# SPEEDuino_v1_0.net
KiCad netlist of a schematic drawn in EAGLE
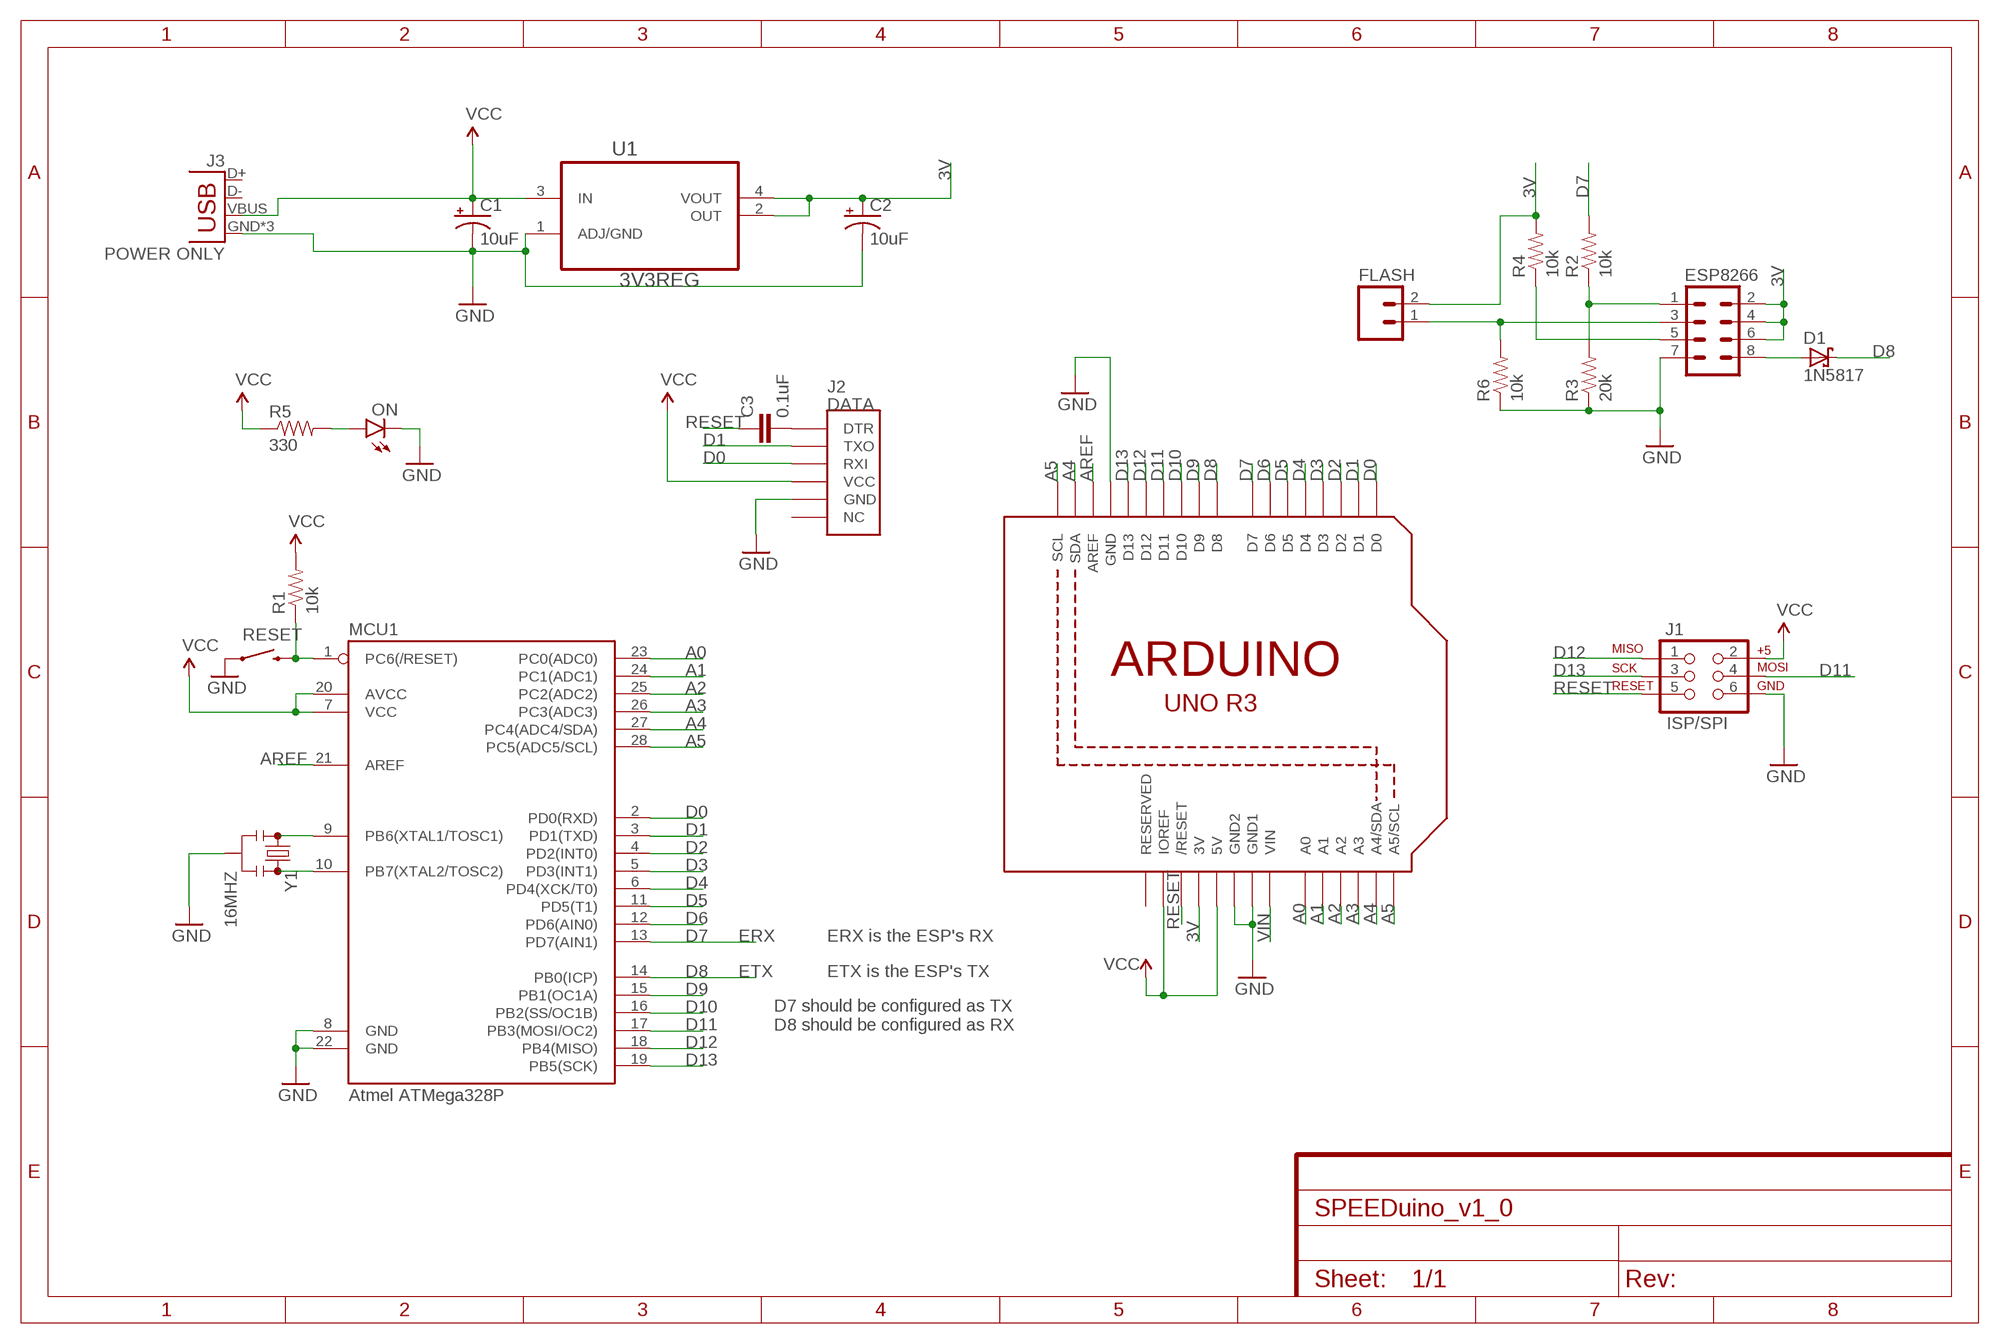
[diagram p0: schematic, sheet 1]

(export (version "E")
  (design (tool "Eeschema 10.0.6"))
  (components
    (comp (ref "C1")
      (value "10uF")
      (footprint "eagle-import:EIA3216-KIT")
      (libsource (lib "eagle-import") (part "CAP_POL1206-KIT"))
    )
    (comp (ref "C2")
      (value "10uF")
      (footprint "eagle-import:EIA3216-KIT")
      (libsource (lib "eagle-import") (part "CAP_POL1206-KIT"))
    )
    (comp (ref "C3")
      (value "0.1uF")
      (footprint "eagle-import:1206")
      (libsource (lib "eagle-import") (part "CAP1206"))
    )
    (comp (ref "D1")
      (value "1N5817")
      (footprint "eagle-import:DO41-10")
      (libsource (lib "eagle-import") (part "1N5817"))
    )
    (comp (ref "ESP8266")
      (value "M04X2")
      (footprint "eagle-import:2X4")
      (libsource (lib "eagle-import") (part "M04X2"))
    )
    (comp (ref "FLASH")
      (value "M02LOCK")
      (footprint "eagle-import:1X02_LOCK")
      (libsource (lib "eagle-import") (part "M02LOCK"))
    )
    (comp (ref "J1")
      (value "ISP/SPI")
      (footprint "eagle-import:2X3")
      (libsource (lib "eagle-import") (part "AVR_SPI_PRG_6PTH"))
    )
    (comp (ref "J2")
      (value "DATA")
      (footprint "eagle-import:CP2102_DEVICE_SIDE")
      (libsource (lib "eagle-import") (part "CP2102_DEVICECP"))
    )
    (comp (ref "J3")
      (value "POWER ONLY")
      (footprint "eagle-import:USB-MICROB")
      (libsource (lib "eagle-import") (part "USB-MICROB"))
    )
    (comp (ref "MCU1")
      (value "Atmel ATMega328P")
      (footprint "eagle-import:DIL28-3")
      (libsource (lib "eagle-import") (part "ATMEGA328P_PDIP"))
    )
    (comp (ref "ON")
      (value "LED3MM")
      (footprint "eagle-import:LED3MM")
      (libsource (lib "eagle-import") (part "LED3MM"))
    )
    (comp (ref "R1")
      (value "10k")
      (footprint "eagle-import:1206")
      (libsource (lib "eagle-import") (part "RESISTOR1206"))
    )
    (comp (ref "R2")
      (value "10k")
      (footprint "eagle-import:1206")
      (libsource (lib "eagle-import") (part "RESISTOR1206"))
    )
    (comp (ref "R3")
      (value "20k")
      (footprint "eagle-import:1206")
      (libsource (lib "eagle-import") (part "RESISTOR1206"))
    )
    (comp (ref "R4")
      (value "10k")
      (footprint "eagle-import:1206")
      (libsource (lib "eagle-import") (part "RESISTOR1206"))
    )
    (comp (ref "R5")
      (value "330")
      (footprint "eagle-import:1206")
      (libsource (lib "eagle-import") (part "RESISTOR1206"))
    )
    (comp (ref "R6")
      (value "10k")
      (footprint "eagle-import:1206")
      (libsource (lib "eagle-import") (part "RESISTOR1206"))
    )
    (comp (ref "RESET")
      (value "SWITCH-MOMENTARY-2PTH")
      (footprint "eagle-import:TACTILE-PTH")
      (libsource (lib "eagle-import") (part "SWITCH-MOMENTARY-2PTH"))
    )
    (comp (ref "U1")
      (value "3V3REG")
      (footprint "eagle-import:SOT230P696X180-4N")
      (fields (field (name "MPN") "LM1117MP-3.3"))
      (libsource (lib "eagle-import") (part "LM1117MP-3.3"))
    )
    (comp (ref "U2")
      (value "ARDUINOR3-DIMENSION")
      (footprint "eagle-import:ARDUINOR3")
      (libsource (lib "eagle-import") (part "ARDUINOR3-DIMENSION"))
    )
    (comp (ref "Y1")
      (value "16MHZ")
      (footprint "eagle-import:RESONATOR-SMD")
      (libsource (lib "eagle-import") (part "RESONATOR16MHZ"))
    )
  )
  (nets
    (net (code "1") (name "/3V") (class "Default")
      (node (ref "C2") (pin "A") (pinfunction "+_A") (pintype "passive"))
      (node (ref "ESP8266") (pin "2") (pinfunction "2_2") (pintype "passive"))
      (node (ref "ESP8266") (pin "4") (pinfunction "4_4") (pintype "passive"))
      (node (ref "ESP8266") (pin "6") (pinfunction "6_6") (pintype "passive"))
      (node (ref "FLASH") (pin "2") (pinfunction "2_2") (pintype "passive"))
      (node (ref "R4") (pin "2") (pinfunction "2_2") (pintype "passive"))
      (node (ref "U1") (pin "2") (pinfunction "OUT_2") (pintype "output"))
      (node (ref "U1") (pin "4") (pinfunction "VOUT_4") (pintype "output"))
      (node (ref "U2") (pin "3V") (pinfunction "3V_3V") (pintype "power_in"))
    )
    (net (code "2") (name "/A0") (class "Default")
      (node (ref "MCU1") (pin "23") (pinfunction "PC0(ADC0)_23") (pintype "bidirectional"))
      (node (ref "U2") (pin "A0") (pinfunction "A0_A0") (pintype "bidirectional"))
    )
    (net (code "3") (name "/A1") (class "Default")
      (node (ref "MCU1") (pin "24") (pinfunction "PC1(ADC1)_24") (pintype "bidirectional"))
      (node (ref "U2") (pin "A1") (pinfunction "A1_A1") (pintype "bidirectional"))
    )
    (net (code "4") (name "/A2") (class "Default")
      (node (ref "MCU1") (pin "25") (pinfunction "PC2(ADC2)_25") (pintype "bidirectional"))
      (node (ref "U2") (pin "A2") (pinfunction "A2_A2") (pintype "bidirectional"))
    )
    (net (code "5") (name "/A3") (class "Default")
      (node (ref "MCU1") (pin "26") (pinfunction "PC3(ADC3)_26") (pintype "bidirectional"))
      (node (ref "U2") (pin "A3") (pinfunction "A3_A3") (pintype "bidirectional"))
    )
    (net (code "6") (name "/A4") (class "Default")
      (node (ref "MCU1") (pin "27") (pinfunction "PC4(ADC4/SDA)_27") (pintype "bidirectional"))
      (node (ref "U2") (pin "A4") (pinfunction "A4/SDA_A4") (pintype "bidirectional"))
      (node (ref "U2") (pin "SDA") (pinfunction "SDA_SDA") (pintype "bidirectional"))
    )
    (net (code "7") (name "/A5") (class "Default")
      (node (ref "MCU1") (pin "28") (pinfunction "PC5(ADC5/SCL)_28") (pintype "bidirectional"))
      (node (ref "U2") (pin "A5") (pinfunction "A5/SCL_A5") (pintype "bidirectional"))
      (node (ref "U2") (pin "SCL") (pinfunction "SCL_SCL") (pintype "bidirectional"))
    )
    (net (code "8") (name "/AREF") (class "Default")
      (node (ref "MCU1") (pin "21") (pinfunction "AREF_21") (pintype "bidirectional"))
      (node (ref "U2") (pin "AREF") (pinfunction "AREF_AREF") (pintype "bidirectional"))
    )
    (net (code "9") (name "/D0") (class "Default")
      (node (ref "J2") (pin "P$3") (pinfunction "RXI_P$3") (pintype "bidirectional"))
      (node (ref "MCU1") (pin "2") (pinfunction "PD0(RXD)_2") (pintype "bidirectional"))
      (node (ref "U2") (pin "D0") (pinfunction "D0_D0") (pintype "bidirectional"))
    )
    (net (code "10") (name "/D1") (class "Default")
      (node (ref "J2") (pin "P$2") (pinfunction "TXO_P$2") (pintype "bidirectional"))
      (node (ref "MCU1") (pin "3") (pinfunction "PD1(TXD)_3") (pintype "bidirectional"))
      (node (ref "U2") (pin "D1") (pinfunction "D1_D1") (pintype "bidirectional"))
    )
    (net (code "11") (name "/D2") (class "Default")
      (node (ref "MCU1") (pin "4") (pinfunction "PD2(INT0)_4") (pintype "bidirectional"))
      (node (ref "U2") (pin "D2") (pinfunction "D2_D2") (pintype "bidirectional"))
    )
    (net (code "12") (name "/D3") (class "Default")
      (node (ref "MCU1") (pin "5") (pinfunction "PD3(INT1)_5") (pintype "bidirectional"))
      (node (ref "U2") (pin "D3") (pinfunction "D3_D3") (pintype "bidirectional"))
    )
    (net (code "13") (name "/D4") (class "Default")
      (node (ref "MCU1") (pin "6") (pinfunction "PD4(XCK/T0)_6") (pintype "bidirectional"))
      (node (ref "U2") (pin "D4") (pinfunction "D4_D4") (pintype "bidirectional"))
    )
    (net (code "14") (name "/D5") (class "Default")
      (node (ref "MCU1") (pin "11") (pinfunction "PD5(T1)_11") (pintype "bidirectional"))
      (node (ref "U2") (pin "D5") (pinfunction "D5_D5") (pintype "bidirectional"))
    )
    (net (code "15") (name "/D6") (class "Default")
      (node (ref "MCU1") (pin "12") (pinfunction "PD6(AIN0)_12") (pintype "bidirectional"))
      (node (ref "U2") (pin "D6") (pinfunction "D6_D6") (pintype "bidirectional"))
    )
    (net (code "16") (name "/D7") (class "Default")
      (node (ref "MCU1") (pin "13") (pinfunction "PD7(AIN1)_13") (pintype "bidirectional"))
      (node (ref "R2") (pin "2") (pinfunction "2_2") (pintype "passive"))
      (node (ref "U2") (pin "D7") (pinfunction "D7_D7") (pintype "bidirectional"))
    )
    (net (code "17") (name "/D8") (class "Default")
      (node (ref "D1") (pin "C") (pinfunction "C_C") (pintype "passive"))
      (node (ref "MCU1") (pin "14") (pinfunction "PB0(ICP)_14") (pintype "bidirectional"))
      (node (ref "U2") (pin "D8") (pinfunction "D8_D8") (pintype "bidirectional"))
    )
    (net (code "18") (name "/D9") (class "Default")
      (node (ref "MCU1") (pin "15") (pinfunction "PB1(OC1A)_15") (pintype "bidirectional"))
      (node (ref "U2") (pin "D9") (pinfunction "D9_D9") (pintype "bidirectional"))
    )
    (net (code "19") (name "/D10") (class "Default")
      (node (ref "MCU1") (pin "16") (pinfunction "PB2(SS/OC1B)_16") (pintype "bidirectional"))
      (node (ref "U2") (pin "D10") (pinfunction "D10_D10") (pintype "bidirectional"))
    )
    (net (code "20") (name "/D11") (class "Default")
      (node (ref "J1") (pin "4") (pinfunction "4_4") (pintype "passive"))
      (node (ref "MCU1") (pin "17") (pinfunction "PB3(MOSI/OC2)_17") (pintype "bidirectional"))
      (node (ref "U2") (pin "D11") (pinfunction "D11_D11") (pintype "bidirectional"))
    )
    (net (code "21") (name "/D12") (class "Default")
      (node (ref "J1") (pin "1") (pinfunction "1_1") (pintype "passive"))
      (node (ref "MCU1") (pin "18") (pinfunction "PB4(MISO)_18") (pintype "bidirectional"))
      (node (ref "U2") (pin "D12") (pinfunction "D12_D12") (pintype "bidirectional"))
    )
    (net (code "22") (name "/D13") (class "Default")
      (node (ref "J1") (pin "3") (pinfunction "3_3") (pintype "passive"))
      (node (ref "MCU1") (pin "19") (pinfunction "PB5(SCK)_19") (pintype "bidirectional"))
      (node (ref "U2") (pin "D13") (pinfunction "D13_D13") (pintype "bidirectional"))
    )
    (net (code "23") (name "/RESET") (class "Default")
      (node (ref "C3") (pin "1") (pinfunction "1_1") (pintype "passive"))
      (node (ref "J1") (pin "5") (pinfunction "5_5") (pintype "passive"))
      (node (ref "MCU1") (pin "1") (pinfunction "PC6(/RESET)_1") (pintype "bidirectional"))
      (node (ref "R1") (pin "1") (pinfunction "1_1") (pintype "passive"))
      (node (ref "RESET") (pin "3") (pinfunction "2_3") (pintype "passive"))
      (node (ref "U2") (pin "RESET") (pinfunction "/RESET_RESET") (pintype "bidirectional"))
    )
    (net (code "24") (name "/VIN") (class "Default")
      (node (ref "U2") (pin "VIN") (pinfunction "VIN_VIN") (pintype "power_in"))
    )
    (net (code "25") (name "GND") (class "Default")
      (node (ref "C1") (pin "C") (pinfunction "-_C") (pintype "passive"))
      (node (ref "C2") (pin "C") (pinfunction "-_C") (pintype "passive"))
      (node (ref "ESP8266") (pin "7") (pinfunction "7_7") (pintype "passive"))
      (node (ref "J1") (pin "6") (pinfunction "6_6") (pintype "passive"))
      (node (ref "J2") (pin "P$5") (pinfunction "GND_P$5") (pintype "bidirectional"))
      (node (ref "J3") (pin "GND") (pinfunction "GND_GND") (pintype "bidirectional"))
      (node (ref "J3") (pin "MT1") (pinfunction "GND_MT1") (pintype "bidirectional"))
      (node (ref "J3") (pin "MT2") (pinfunction "GND_MT2") (pintype "bidirectional"))
      (node (ref "MCU1") (pin "22") (pinfunction "GND_22") (pintype "bidirectional"))
      (node (ref "MCU1") (pin "8") (pinfunction "GND_8") (pintype "bidirectional"))
      (node (ref "ON") (pin "K") (pinfunction "C_K") (pintype "passive"))
      (node (ref "R3") (pin "1") (pinfunction "1_1") (pintype "passive"))
      (node (ref "R6") (pin "1") (pinfunction "1_1") (pintype "passive"))
      (node (ref "RESET") (pin "1") (pinfunction "1_1") (pintype "passive"))
      (node (ref "U1") (pin "1") (pinfunction "ADJ/GND_1") (pintype "passive"))
      (node (ref "U2") (pin "GND") (pinfunction "GND_GND") (pintype "power_in"))
      (node (ref "U2") (pin "GND1") (pinfunction "GND1_GND1") (pintype "power_in"))
      (node (ref "U2") (pin "GND2") (pinfunction "GND2_GND2") (pintype "power_in"))
      (node (ref "Y1") (pin "2") (pinfunction "2_2") (pintype "passive"))
    )
    (net (code "26") (name "Net-(D1-PadA)") (class "Default")
      (node (ref "D1") (pin "A") (pinfunction "A_A") (pintype "passive"))
      (node (ref "ESP8266") (pin "8") (pinfunction "8_8") (pintype "passive"))
    )
    (net (code "27") (name "Net-(ESP8266-Pad1)") (class "Default")
      (node (ref "ESP8266") (pin "1") (pinfunction "1_1") (pintype "passive"))
      (node (ref "R2") (pin "1") (pinfunction "1_1") (pintype "passive"))
      (node (ref "R3") (pin "2") (pinfunction "2_2") (pintype "passive"))
    )
    (net (code "28") (name "Net-(ESP8266-Pad3)") (class "Default")
      (node (ref "ESP8266") (pin "3") (pinfunction "3_3") (pintype "passive"))
      (node (ref "FLASH") (pin "1") (pinfunction "1_1") (pintype "passive"))
      (node (ref "R6") (pin "2") (pinfunction "2_2") (pintype "passive"))
    )
    (net (code "29") (name "Net-(ESP8266-Pad5)") (class "Default")
      (node (ref "ESP8266") (pin "5") (pinfunction "5_5") (pintype "passive"))
      (node (ref "R4") (pin "1") (pinfunction "1_1") (pintype "passive"))
    )
    (net (code "30") (name "Net-(J2-DTR)") (class "Default")
      (node (ref "C3") (pin "2") (pinfunction "2_2") (pintype "passive"))
      (node (ref "J2") (pin "P$1") (pinfunction "DTR_P$1") (pintype "bidirectional"))
    )
    (net (code "31") (name "Net-(MCU1-PB6(XTAL1{slash}TOSC1))") (class "Default")
      (node (ref "MCU1") (pin "9") (pinfunction "PB6(XTAL1/TOSC1)_9") (pintype "bidirectional"))
      (node (ref "Y1") (pin "1") (pinfunction "1_1") (pintype "passive"))
    )
    (net (code "32") (name "Net-(MCU1-PB7(XTAL2{slash}TOSC2))") (class "Default")
      (node (ref "MCU1") (pin "10") (pinfunction "PB7(XTAL2/TOSC2)_10") (pintype "bidirectional"))
      (node (ref "Y1") (pin "3") (pinfunction "3_3") (pintype "passive"))
    )
    (net (code "33") (name "Net-(ON-PadA)") (class "Default")
      (node (ref "ON") (pin "A") (pinfunction "A_A") (pintype "passive"))
      (node (ref "R5") (pin "2") (pinfunction "2_2") (pintype "passive"))
    )
    (net (code "34") (name "VCC") (class "Default")
      (node (ref "C1") (pin "A") (pinfunction "+_A") (pintype "passive"))
      (node (ref "J1") (pin "2") (pinfunction "2_2") (pintype "passive"))
      (node (ref "J2") (pin "P$4") (pinfunction "VCC_P$4") (pintype "bidirectional"))
      (node (ref "J3") (pin "VBUS") (pinfunction "VBUS_VBUS") (pintype "bidirectional"))
      (node (ref "MCU1") (pin "20") (pinfunction "AVCC_20") (pintype "bidirectional"))
      (node (ref "MCU1") (pin "7") (pinfunction "VCC_7") (pintype "bidirectional"))
      (node (ref "R1") (pin "2") (pinfunction "2_2") (pintype "passive"))
      (node (ref "R5") (pin "1") (pinfunction "1_1") (pintype "passive"))
      (node (ref "U1") (pin "3") (pinfunction "IN_3") (pintype "input"))
      (node (ref "U2") (pin "5V") (pinfunction "5V_5V") (pintype "power_in"))
      (node (ref "U2") (pin "IOREF") (pinfunction "IOREF_IOREF") (pintype "output"))
    )
    (net (code "35") (name "unconnected-(J2-NC-PadP$6)") (class "Default")
      (node (ref "J2") (pin "P$6") (pinfunction "NC_P$6") (pintype "bidirectional"))
    )
    (net (code "36") (name "unconnected-(J3-PadD+)") (class "Default")
      (node (ref "J3") (pin "D+") (pinfunction "D+_D+") (pintype "bidirectional"))
    )
    (net (code "37") (name "unconnected-(J3-PadD-)") (class "Default")
      (node (ref "J3") (pin "D-") (pinfunction "D-_D-") (pintype "bidirectional"))
    )
    (net (code "38") (name "unconnected-(U2-PadRESERVED)") (class "Default")
      (node (ref "U2") (pin "RESERVED") (pinfunction "RESERVED_RESERVED") (pintype "no_connect"))
    )
  )
)
